# INA226_breakout_v00.net
KiCad netlist of a schematic drawn in EAGLE
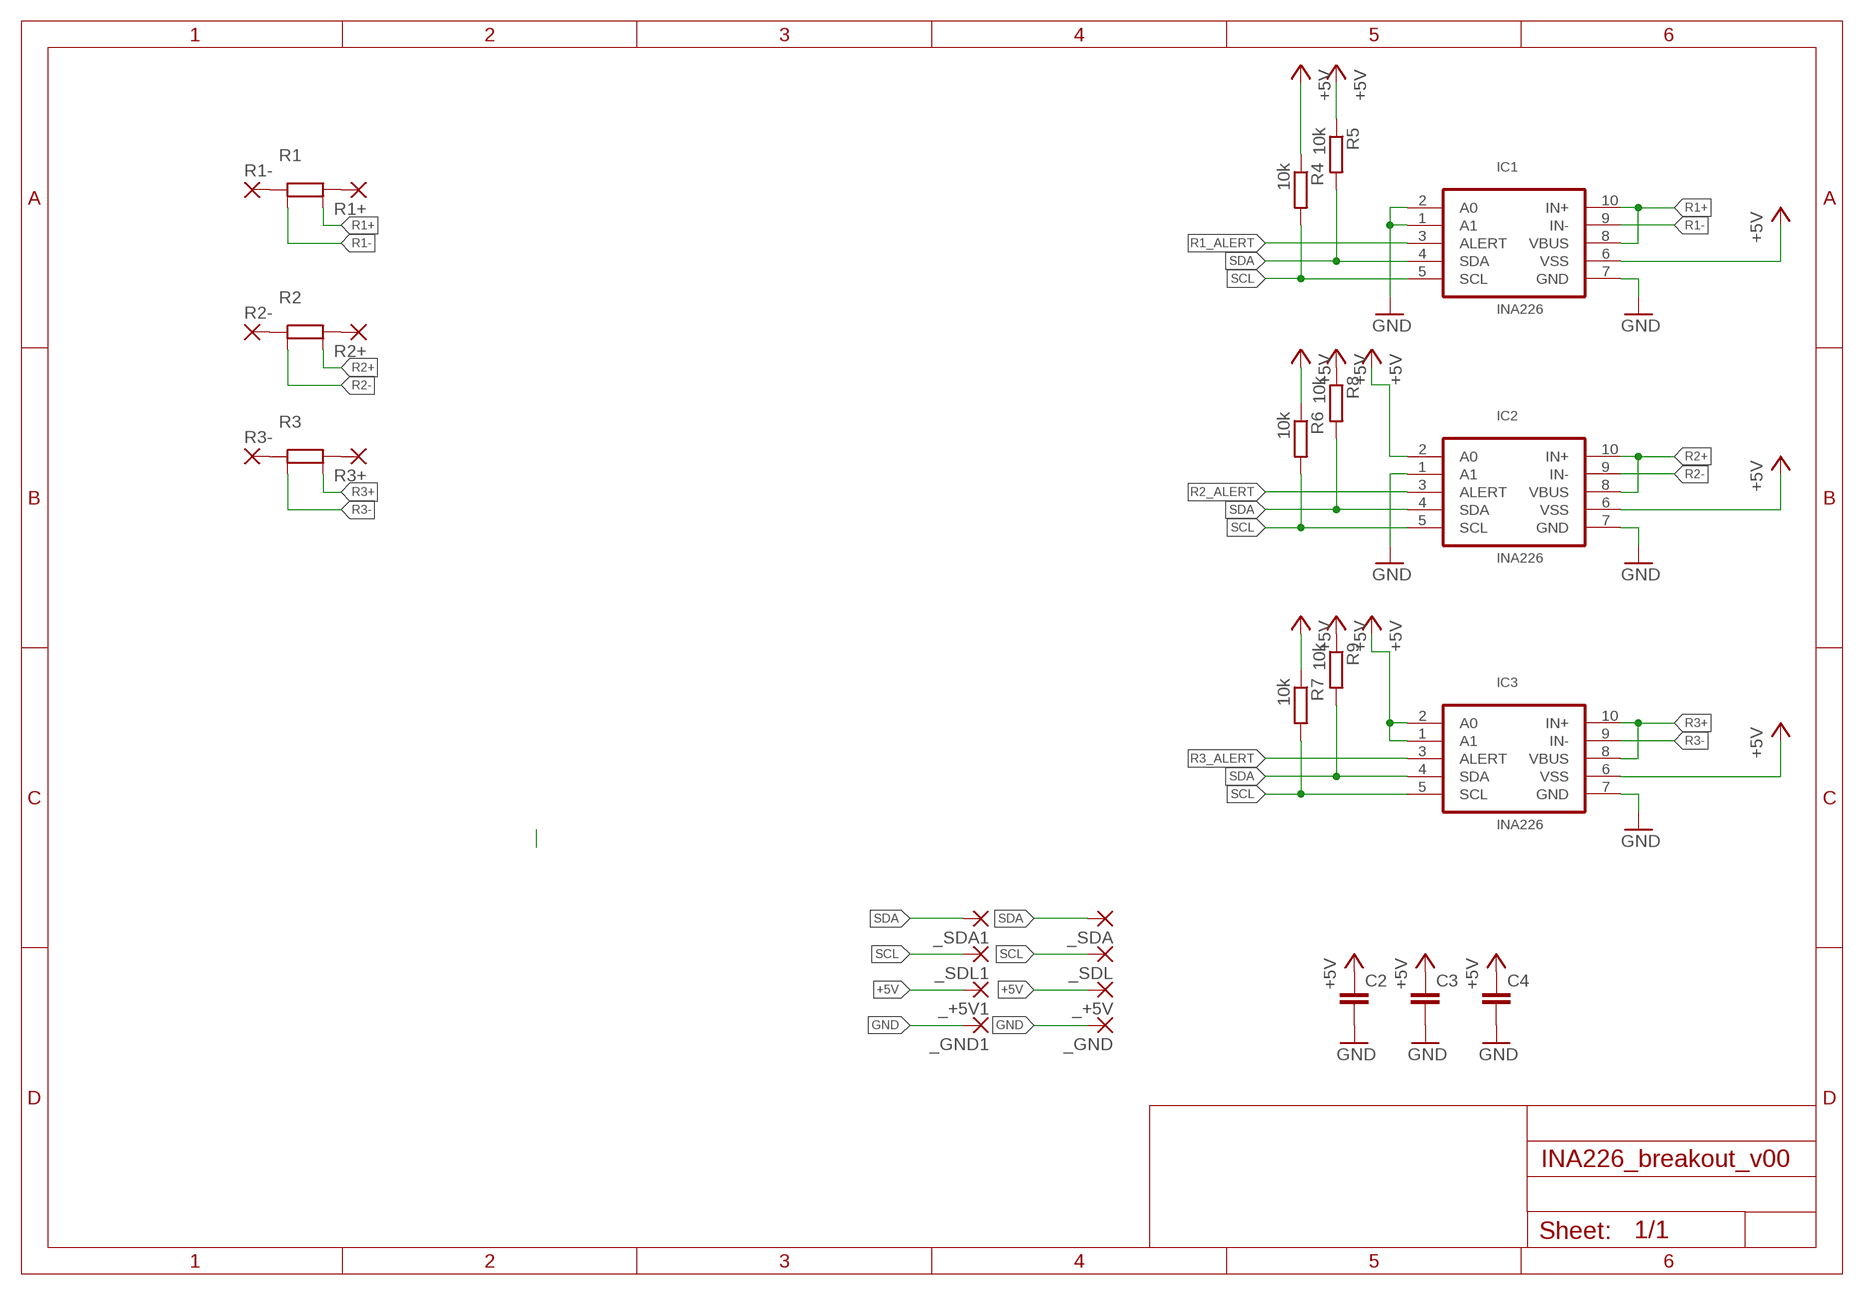
[diagram p0: schematic, sheet 1]

(export (version "E")
  (design (tool "Eeschema 10.0.6"))
  (components
    (comp (ref "C2")
      (value "C-EUC0805")
      (footprint "eagle-import:C0805")
      (libsource (lib "eagle-import") (part "C-EUC0805"))
    )
    (comp (ref "C3")
      (value "C-EUC0805")
      (footprint "eagle-import:C0805")
      (libsource (lib "eagle-import") (part "C-EUC0805"))
    )
    (comp (ref "C4")
      (value "C-EUC0603")
      (footprint "eagle-import:C0603")
      (libsource (lib "eagle-import") (part "C-EUC0603"))
    )
    (comp (ref "IC1")
      (value "INA226")
      (footprint "eagle-import:VSSOP-10")
      (libsource (lib "eagle-import") (part "INA226"))
    )
    (comp (ref "IC2")
      (value "INA226")
      (footprint "eagle-import:VSSOP-10")
      (libsource (lib "eagle-import") (part "INA226"))
    )
    (comp (ref "IC3")
      (value "INA226")
      (footprint "eagle-import:VSSOP-10")
      (libsource (lib "eagle-import") (part "INA226"))
    )
    (comp (ref "R1")
      (value "BOURNS_CSS4J-4026")
      (footprint "eagle-import:BOURNS_CSS4J-4026")
      (libsource (lib "eagle-import") (part "BOURNS_CSS4J-4026"))
    )
    (comp (ref "R1+")
      (value "3,81/1,4")
      (footprint "eagle-import:3,81_1,4")
      (libsource (lib "eagle-import") (part "3,81/1,4"))
    )
    (comp (ref "R1-")
      (value "3,81/1,4")
      (footprint "eagle-import:3,81_1,4")
      (libsource (lib "eagle-import") (part "3,81/1,4"))
    )
    (comp (ref "R2")
      (value "BOURNS_CSS4J-4026")
      (footprint "eagle-import:BOURNS_CSS4J-4026")
      (libsource (lib "eagle-import") (part "BOURNS_CSS4J-4026"))
    )
    (comp (ref "R2+")
      (value "3,81/1,4")
      (footprint "eagle-import:3,81_1,4")
      (libsource (lib "eagle-import") (part "3,81/1,4"))
    )
    (comp (ref "R2-")
      (value "3,81/1,4")
      (footprint "eagle-import:3,81_1,4")
      (libsource (lib "eagle-import") (part "3,81/1,4"))
    )
    (comp (ref "R3")
      (value "BOURNS_CSS4J-4026")
      (footprint "eagle-import:BOURNS_CSS4J-4026")
      (libsource (lib "eagle-import") (part "BOURNS_CSS4J-4026"))
    )
    (comp (ref "R3+")
      (value "3,81/1,4")
      (footprint "eagle-import:3,81_1,4")
      (libsource (lib "eagle-import") (part "3,81/1,4"))
    )
    (comp (ref "R3-")
      (value "3,81/1,4")
      (footprint "eagle-import:3,81_1,4")
      (libsource (lib "eagle-import") (part "3,81/1,4"))
    )
    (comp (ref "R4")
      (value "10k")
      (footprint "eagle-import:M0805")
      (libsource (lib "eagle-import") (part "R-EU_M0805"))
    )
    (comp (ref "R5")
      (value "10k")
      (footprint "eagle-import:M0805")
      (libsource (lib "eagle-import") (part "R-EU_M0805"))
    )
    (comp (ref "R6")
      (value "10k")
      (footprint "eagle-import:M0805")
      (libsource (lib "eagle-import") (part "R-EU_M0805"))
    )
    (comp (ref "R7")
      (value "10k")
      (footprint "eagle-import:M0805")
      (libsource (lib "eagle-import") (part "R-EU_M0805"))
    )
    (comp (ref "R8")
      (value "10k")
      (footprint "eagle-import:M0805")
      (libsource (lib "eagle-import") (part "R-EU_M0805"))
    )
    (comp (ref "R9")
      (value "10k")
      (footprint "eagle-import:M0805")
      (libsource (lib "eagle-import") (part "R-EU_M0805"))
    )
    (comp (ref "_+5V")
      (value "1,6/0,9")
      (footprint "eagle-import:1,6_0,9")
      (libsource (lib "eagle-import") (part "1,6/0,9"))
    )
    (comp (ref "_+5V1")
      (value "1,6/0,9")
      (footprint "eagle-import:1,6_0,9")
      (libsource (lib "eagle-import") (part "1,6/0,9"))
    )
    (comp (ref "_GND")
      (value "1,6/0,9")
      (footprint "eagle-import:1,6_0,9")
      (libsource (lib "eagle-import") (part "1,6/0,9"))
    )
    (comp (ref "_GND1")
      (value "1,6/0,9")
      (footprint "eagle-import:1,6_0,9")
      (libsource (lib "eagle-import") (part "1,6/0,9"))
    )
    (comp (ref "_SDA")
      (value "1,6/0,9")
      (footprint "eagle-import:1,6_0,9")
      (libsource (lib "eagle-import") (part "1,6/0,9"))
    )
    (comp (ref "_SDA1")
      (value "1,6/0,9")
      (footprint "eagle-import:1,6_0,9")
      (libsource (lib "eagle-import") (part "1,6/0,9"))
    )
    (comp (ref "_SDL")
      (value "1,6/0,9")
      (footprint "eagle-import:1,6_0,9")
      (libsource (lib "eagle-import") (part "1,6/0,9"))
    )
    (comp (ref "_SDL1")
      (value "1,6/0,9")
      (footprint "eagle-import:1,6_0,9")
      (libsource (lib "eagle-import") (part "1,6/0,9"))
    )
  )
  (nets
    (net (code "1") (name "+5V") (class "Default")
      (node (ref "C2") (pin "1") (pinfunction "1_1") (pintype "passive"))
      (node (ref "C3") (pin "1") (pinfunction "1_1") (pintype "passive"))
      (node (ref "C4") (pin "1") (pinfunction "1_1") (pintype "passive"))
      (node (ref "IC1") (pin "6") (pinfunction "VSS_6") (pintype "power_in"))
      (node (ref "IC2") (pin "2") (pinfunction "A0_2") (pintype "input"))
      (node (ref "IC2") (pin "6") (pinfunction "VSS_6") (pintype "power_in"))
      (node (ref "IC3") (pin "1") (pinfunction "A1_1") (pintype "input"))
      (node (ref "IC3") (pin "2") (pinfunction "A0_2") (pintype "input"))
      (node (ref "IC3") (pin "6") (pinfunction "VSS_6") (pintype "power_in"))
      (node (ref "R4") (pin "1") (pinfunction "1_1") (pintype "passive"))
      (node (ref "R5") (pin "1") (pinfunction "1_1") (pintype "passive"))
      (node (ref "R6") (pin "1") (pinfunction "1_1") (pintype "passive"))
      (node (ref "R7") (pin "1") (pinfunction "1_1") (pintype "passive"))
      (node (ref "R8") (pin "1") (pinfunction "1_1") (pintype "passive"))
      (node (ref "R9") (pin "1") (pinfunction "1_1") (pintype "passive"))
      (node (ref "_+5V") (pin "1") (pinfunction "P_1") (pintype "passive"))
      (node (ref "_+5V1") (pin "1") (pinfunction "P_1") (pintype "passive"))
    )
    (net (code "2") (name "GND") (class "Default")
      (node (ref "C2") (pin "2") (pinfunction "2_2") (pintype "passive"))
      (node (ref "C3") (pin "2") (pinfunction "2_2") (pintype "passive"))
      (node (ref "C4") (pin "2") (pinfunction "2_2") (pintype "passive"))
      (node (ref "IC1") (pin "1") (pinfunction "A1_1") (pintype "input"))
      (node (ref "IC1") (pin "2") (pinfunction "A0_2") (pintype "input"))
      (node (ref "IC1") (pin "7") (pinfunction "GND_7") (pintype "power_in"))
      (node (ref "IC2") (pin "1") (pinfunction "A1_1") (pintype "input"))
      (node (ref "IC2") (pin "7") (pinfunction "GND_7") (pintype "power_in"))
      (node (ref "IC3") (pin "7") (pinfunction "GND_7") (pintype "power_in"))
      (node (ref "_GND") (pin "1") (pinfunction "P_1") (pintype "passive"))
      (node (ref "_GND1") (pin "1") (pinfunction "P_1") (pintype "passive"))
    )
    (net (code "3") (name "Net-(R1+-P)") (class "Default")
      (node (ref "R1") (pin "P$2") (pinfunction "2_P$2") (pintype "passive"))
      (node (ref "R1+") (pin "1") (pinfunction "P_1") (pintype "passive"))
    )
    (net (code "4") (name "Net-(R1--P)") (class "Default")
      (node (ref "R1") (pin "P$1") (pinfunction "1_P$1") (pintype "passive"))
      (node (ref "R1-") (pin "1") (pinfunction "P_1") (pintype "passive"))
    )
    (net (code "5") (name "Net-(R2+-P)") (class "Default")
      (node (ref "R2") (pin "P$2") (pinfunction "2_P$2") (pintype "passive"))
      (node (ref "R2+") (pin "1") (pinfunction "P_1") (pintype "passive"))
    )
    (net (code "6") (name "Net-(R2--P)") (class "Default")
      (node (ref "R2") (pin "P$1") (pinfunction "1_P$1") (pintype "passive"))
      (node (ref "R2-") (pin "1") (pinfunction "P_1") (pintype "passive"))
    )
    (net (code "7") (name "Net-(R3+-P)") (class "Default")
      (node (ref "R3") (pin "P$2") (pinfunction "2_P$2") (pintype "passive"))
      (node (ref "R3+") (pin "1") (pinfunction "P_1") (pintype "passive"))
    )
    (net (code "8") (name "Net-(R3--P)") (class "Default")
      (node (ref "R3") (pin "P$1") (pinfunction "1_P$1") (pintype "passive"))
      (node (ref "R3-") (pin "1") (pinfunction "P_1") (pintype "passive"))
    )
    (net (code "9") (name "R1+") (class "Default")
      (node (ref "IC1") (pin "10") (pinfunction "IN+_10") (pintype "input"))
      (node (ref "IC1") (pin "8") (pinfunction "VBUS_8") (pintype "passive"))
      (node (ref "R1") (pin "PS$2") (pinfunction "S2_PS$2") (pintype "passive"))
    )
    (net (code "10") (name "R1-") (class "Default")
      (node (ref "IC1") (pin "9") (pinfunction "IN-_9") (pintype "input"))
      (node (ref "R1") (pin "PS$1") (pinfunction "S1_PS$1") (pintype "passive"))
    )
    (net (code "11") (name "R1_ALERT") (class "Default")
      (node (ref "IC1") (pin "3") (pinfunction "ALERT_3") (pintype "input"))
    )
    (net (code "12") (name "R2+") (class "Default")
      (node (ref "IC2") (pin "10") (pinfunction "IN+_10") (pintype "input"))
      (node (ref "IC2") (pin "8") (pinfunction "VBUS_8") (pintype "passive"))
      (node (ref "R2") (pin "PS$2") (pinfunction "S2_PS$2") (pintype "passive"))
    )
    (net (code "13") (name "R2-") (class "Default")
      (node (ref "IC2") (pin "9") (pinfunction "IN-_9") (pintype "input"))
      (node (ref "R2") (pin "PS$1") (pinfunction "S1_PS$1") (pintype "passive"))
    )
    (net (code "14") (name "R2_ALERT") (class "Default")
      (node (ref "IC2") (pin "3") (pinfunction "ALERT_3") (pintype "input"))
    )
    (net (code "15") (name "R3+") (class "Default")
      (node (ref "IC3") (pin "10") (pinfunction "IN+_10") (pintype "input"))
      (node (ref "IC3") (pin "8") (pinfunction "VBUS_8") (pintype "passive"))
      (node (ref "R3") (pin "PS$2") (pinfunction "S2_PS$2") (pintype "passive"))
    )
    (net (code "16") (name "R3-") (class "Default")
      (node (ref "IC3") (pin "9") (pinfunction "IN-_9") (pintype "input"))
      (node (ref "R3") (pin "PS$1") (pinfunction "S1_PS$1") (pintype "passive"))
    )
    (net (code "17") (name "R3_ALERT") (class "Default")
      (node (ref "IC3") (pin "3") (pinfunction "ALERT_3") (pintype "input"))
    )
    (net (code "18") (name "SCL") (class "Default")
      (node (ref "IC1") (pin "5") (pinfunction "SCL_5") (pintype "input"))
      (node (ref "IC2") (pin "5") (pinfunction "SCL_5") (pintype "input"))
      (node (ref "IC3") (pin "5") (pinfunction "SCL_5") (pintype "input"))
      (node (ref "R4") (pin "2") (pinfunction "2_2") (pintype "passive"))
      (node (ref "R6") (pin "2") (pinfunction "2_2") (pintype "passive"))
      (node (ref "R7") (pin "2") (pinfunction "2_2") (pintype "passive"))
      (node (ref "_SDL") (pin "1") (pinfunction "P_1") (pintype "passive"))
      (node (ref "_SDL1") (pin "1") (pinfunction "P_1") (pintype "passive"))
    )
    (net (code "19") (name "SDA") (class "Default")
      (node (ref "IC1") (pin "4") (pinfunction "SDA_4") (pintype "input"))
      (node (ref "IC2") (pin "4") (pinfunction "SDA_4") (pintype "input"))
      (node (ref "IC3") (pin "4") (pinfunction "SDA_4") (pintype "input"))
      (node (ref "R5") (pin "2") (pinfunction "2_2") (pintype "passive"))
      (node (ref "R8") (pin "2") (pinfunction "2_2") (pintype "passive"))
      (node (ref "R9") (pin "2") (pinfunction "2_2") (pintype "passive"))
      (node (ref "_SDA") (pin "1") (pinfunction "P_1") (pintype "passive"))
      (node (ref "_SDA1") (pin "1") (pinfunction "P_1") (pintype "passive"))
    )
  )
)
